# FMC_PWR.net
KiCad netlist of a schematic drawn in Altium Designer
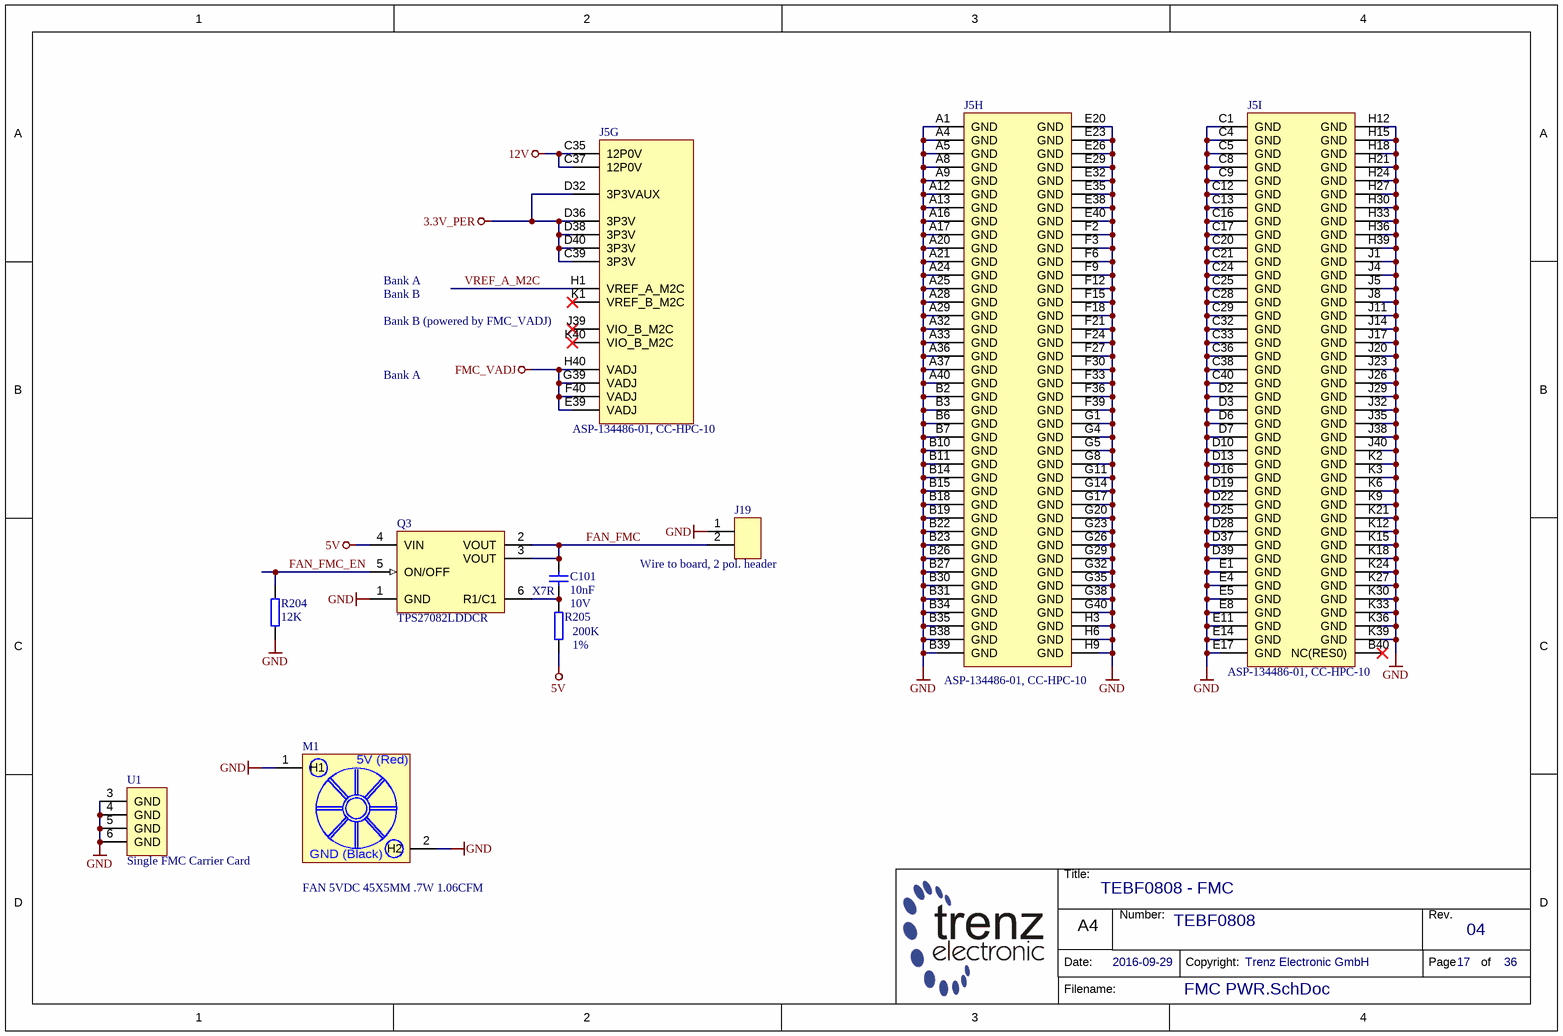
[diagram p0: FMC PWR.SchDoc]

(export (version "E")
  (design (tool "Eeschema 10.0.6"))
  (components
    (comp (ref "C101")
      (value "10nF")
      (footprint "CAPC0603X33N")
      (description "KON 10nF X7R 10V SMD 10%")
      (fields
        (field (name "VOLTAGE") "10V")
        (field (name "TECHNOLOGY") "X7R")
        (field (name "TOLERANCE") "10%")
      )
      (libsource (lib "TE") (part "CAP-NP"))
    )
    (comp (ref "J5")
      (value "ASP-134486-01, CC-HPC-10")
      (footprint "ASP-134486-01B")
      (description "ASP-134486-01 female, CC-HPC-10")
      (libsource (lib "TE") (part "VITA57-FMC-HPC-Layout"))
    )
    (comp (ref "J19")
      (value "Wire to board, 2 pol. header")
      (footprint "Molex22-27-2021")
      (description "Wire to board, 2 pol. header 0°")
      (libsource (lib "TE") (part "CON-2"))
    )
    (comp (ref "M1")
      (value "FAN 5VDC 45X5MM .7W 1.06CFM")
      (footprint "F455B-05MD")
      (libsource (lib "TE") (part "F455B-05MD"))
    )
    (comp (ref "Q3")
      (value "TPS27082LDDCR")
      (footprint "SOT95P280X110-6N")
      (libsource (lib "TE") (part "TPS27082LDDCR"))
    )
    (comp (ref "R204")
      (value "12K")
      (footprint "RESC1005X40N")
      (description "WID SMD 12K 1% 0,063W")
      (fields (field (name "TOLERANCE") "1%"))
      (libsource (lib "TE") (part "RES"))
    )
    (comp (ref "R205")
      (value "200K")
      (footprint "RESC1005X40N")
      (description "WID SMD 200K 1% 0,063W")
      (fields (field (name "TOLERANCE") "1%"))
      (libsource (lib "TE") (part "RES"))
    )
    (comp (ref "U1")
      (value "Single FMC Carrier Card")
      (footprint "FMC-MM-Single-Base")
      (description "FMC-MM-Single PCB Baseboard Snap")
      (libsource (lib "TE") (part "FMC-MM-Single"))
    )
  )
  (nets
    (net (code "1") (name "/FAN_FMC") (class "Default")
      (node (ref "C101") (pin "1") (pinfunction "1_1") (pintype "passive"))
      (node (ref "J19") (pin "2") (pinfunction "2_2") (pintype "passive"))
      (node (ref "Q3") (pin "2") (pinfunction "VOUT_2") (pintype "power_in"))
      (node (ref "Q3") (pin "3") (pinfunction "VOUT_3") (pintype "power_in"))
    )
    (net (code "2") (name "/FAN_FMC_EN") (class "Default")
      (node (ref "Q3") (pin "5") (pinfunction "ON/OFF_5") (pintype "input"))
      (node (ref "R204") (pin "1") (pinfunction "1_1") (pintype "passive"))
    )
    (net (code "3") (name "/VREF_A_M2C") (class "Default")
      (node (ref "J5") (pin "H1") (pinfunction "VREF_A_M2C_H1") (pintype "power_in"))
    )
    (net (code "4") (name "3.3V_PER") (class "Default")
      (node (ref "J5") (pin "C39") (pinfunction "3P3V_C39") (pintype "power_in"))
      (node (ref "J5") (pin "D32") (pinfunction "3P3VAUX_D32") (pintype "power_in"))
      (node (ref "J5") (pin "D36") (pinfunction "3P3V_D36") (pintype "power_in"))
      (node (ref "J5") (pin "D38") (pinfunction "3P3V_D38") (pintype "power_in"))
      (node (ref "J5") (pin "D40") (pinfunction "3P3V_D40") (pintype "power_in"))
    )
    (net (code "5") (name "5V") (class "Default")
      (node (ref "Q3") (pin "4") (pinfunction "VIN_4") (pintype "power_in"))
      (node (ref "R205") (pin "2") (pinfunction "2_2") (pintype "passive"))
    )
    (net (code "6") (name "12V") (class "Default")
      (node (ref "J5") (pin "C35") (pinfunction "12P0V_C35") (pintype "power_in"))
      (node (ref "J5") (pin "C37") (pinfunction "12P0V_C37") (pintype "power_in"))
    )
    (net (code "7") (name "FMC_VADJ") (class "Default")
      (node (ref "J5") (pin "E39") (pinfunction "VADJ_E39") (pintype "power_in"))
      (node (ref "J5") (pin "F40") (pinfunction "VADJ_F40") (pintype "power_in"))
      (node (ref "J5") (pin "G39") (pinfunction "VADJ_G39") (pintype "power_in"))
      (node (ref "J5") (pin "H40") (pinfunction "VADJ_H40") (pintype "power_in"))
    )
    (net (code "8") (name "GND") (class "Default")
      (node (ref "J19") (pin "1") (pinfunction "1_1") (pintype "passive"))
      (node (ref "J5") (pin "A1") (pinfunction "GND_A1") (pintype "power_in"))
      (node (ref "J5") (pin "A12") (pinfunction "GND_A12") (pintype "power_in"))
      (node (ref "J5") (pin "A13") (pinfunction "GND_A13") (pintype "power_in"))
      (node (ref "J5") (pin "A16") (pinfunction "GND_A16") (pintype "power_in"))
      (node (ref "J5") (pin "A17") (pinfunction "GND_A17") (pintype "power_in"))
      (node (ref "J5") (pin "A20") (pinfunction "GND_A20") (pintype "power_in"))
      (node (ref "J5") (pin "A21") (pinfunction "GND_A21") (pintype "power_in"))
      (node (ref "J5") (pin "A24") (pinfunction "GND_A24") (pintype "power_in"))
      (node (ref "J5") (pin "A25") (pinfunction "GND_A25") (pintype "power_in"))
      (node (ref "J5") (pin "A28") (pinfunction "GND_A28") (pintype "power_in"))
      (node (ref "J5") (pin "A29") (pinfunction "GND_A29") (pintype "power_in"))
      (node (ref "J5") (pin "A32") (pinfunction "GND_A32") (pintype "power_in"))
      (node (ref "J5") (pin "A33") (pinfunction "GND_A33") (pintype "power_in"))
      (node (ref "J5") (pin "A36") (pinfunction "GND_A36") (pintype "power_in"))
      (node (ref "J5") (pin "A37") (pinfunction "GND_A37") (pintype "power_in"))
      (node (ref "J5") (pin "A4") (pinfunction "GND_A4") (pintype "power_in"))
      (node (ref "J5") (pin "A40") (pinfunction "GND_A40") (pintype "power_in"))
      (node (ref "J5") (pin "A5") (pinfunction "GND_A5") (pintype "power_in"))
      (node (ref "J5") (pin "A8") (pinfunction "GND_A8") (pintype "power_in"))
      (node (ref "J5") (pin "A9") (pinfunction "GND_A9") (pintype "power_in"))
      (node (ref "J5") (pin "B10") (pinfunction "GND_B10") (pintype "power_in"))
      (node (ref "J5") (pin "B11") (pinfunction "GND_B11") (pintype "power_in"))
      (node (ref "J5") (pin "B14") (pinfunction "GND_B14") (pintype "power_in"))
      (node (ref "J5") (pin "B15") (pinfunction "GND_B15") (pintype "power_in"))
      (node (ref "J5") (pin "B18") (pinfunction "GND_B18") (pintype "power_in"))
      (node (ref "J5") (pin "B19") (pinfunction "GND_B19") (pintype "power_in"))
      (node (ref "J5") (pin "B2") (pinfunction "GND_B2") (pintype "power_in"))
      (node (ref "J5") (pin "B22") (pinfunction "GND_B22") (pintype "power_in"))
      (node (ref "J5") (pin "B23") (pinfunction "GND_B23") (pintype "power_in"))
      (node (ref "J5") (pin "B26") (pinfunction "GND_B26") (pintype "power_in"))
      (node (ref "J5") (pin "B27") (pinfunction "GND_B27") (pintype "power_in"))
      (node (ref "J5") (pin "B3") (pinfunction "GND_B3") (pintype "power_in"))
      (node (ref "J5") (pin "B30") (pinfunction "GND_B30") (pintype "power_in"))
      (node (ref "J5") (pin "B31") (pinfunction "GND_B31") (pintype "power_in"))
      (node (ref "J5") (pin "B34") (pinfunction "GND_B34") (pintype "power_in"))
      (node (ref "J5") (pin "B35") (pinfunction "GND_B35") (pintype "power_in"))
      (node (ref "J5") (pin "B38") (pinfunction "GND_B38") (pintype "power_in"))
      (node (ref "J5") (pin "B39") (pinfunction "GND_B39") (pintype "power_in"))
      (node (ref "J5") (pin "B6") (pinfunction "GND_B6") (pintype "power_in"))
      (node (ref "J5") (pin "B7") (pinfunction "GND_B7") (pintype "power_in"))
      (node (ref "J5") (pin "C1") (pinfunction "GND_C1") (pintype "power_in"))
      (node (ref "J5") (pin "C12") (pinfunction "GND_C12") (pintype "power_in"))
      (node (ref "J5") (pin "C13") (pinfunction "GND_C13") (pintype "power_in"))
      (node (ref "J5") (pin "C16") (pinfunction "GND_C16") (pintype "power_in"))
      (node (ref "J5") (pin "C17") (pinfunction "GND_C17") (pintype "power_in"))
      (node (ref "J5") (pin "C20") (pinfunction "GND_C20") (pintype "power_in"))
      (node (ref "J5") (pin "C21") (pinfunction "GND_C21") (pintype "power_in"))
      (node (ref "J5") (pin "C24") (pinfunction "GND_C24") (pintype "power_in"))
      (node (ref "J5") (pin "C25") (pinfunction "GND_C25") (pintype "power_in"))
      (node (ref "J5") (pin "C28") (pinfunction "GND_C28") (pintype "power_in"))
      (node (ref "J5") (pin "C29") (pinfunction "GND_C29") (pintype "power_in"))
      (node (ref "J5") (pin "C32") (pinfunction "GND_C32") (pintype "power_in"))
      (node (ref "J5") (pin "C33") (pinfunction "GND_C33") (pintype "power_in"))
      (node (ref "J5") (pin "C36") (pinfunction "GND_C36") (pintype "power_in"))
      (node (ref "J5") (pin "C38") (pinfunction "GND_C38") (pintype "power_in"))
      (node (ref "J5") (pin "C4") (pinfunction "GND_C4") (pintype "power_in"))
      (node (ref "J5") (pin "C40") (pinfunction "GND_C40") (pintype "power_in"))
      (node (ref "J5") (pin "C5") (pinfunction "GND_C5") (pintype "power_in"))
      (node (ref "J5") (pin "C8") (pinfunction "GND_C8") (pintype "power_in"))
      (node (ref "J5") (pin "C9") (pinfunction "GND_C9") (pintype "power_in"))
      (node (ref "J5") (pin "D10") (pinfunction "GND_D10") (pintype "power_in"))
      (node (ref "J5") (pin "D13") (pinfunction "GND_D13") (pintype "power_in"))
      (node (ref "J5") (pin "D16") (pinfunction "GND_D16") (pintype "power_in"))
      (node (ref "J5") (pin "D19") (pinfunction "GND_D19") (pintype "power_in"))
      (node (ref "J5") (pin "D2") (pinfunction "GND_D2") (pintype "power_in"))
      (node (ref "J5") (pin "D22") (pinfunction "GND_D22") (pintype "power_in"))
      (node (ref "J5") (pin "D25") (pinfunction "GND_D25") (pintype "power_in"))
      (node (ref "J5") (pin "D28") (pinfunction "GND_D28") (pintype "power_in"))
      (node (ref "J5") (pin "D3") (pinfunction "GND_D3") (pintype "power_in"))
      (node (ref "J5") (pin "D37") (pinfunction "GND_D37") (pintype "power_in"))
      (node (ref "J5") (pin "D39") (pinfunction "GND_D39") (pintype "power_in"))
      (node (ref "J5") (pin "D6") (pinfunction "GND_D6") (pintype "power_in"))
      (node (ref "J5") (pin "D7") (pinfunction "GND_D7") (pintype "power_in"))
      (node (ref "J5") (pin "E1") (pinfunction "GND_E1") (pintype "power_in"))
      (node (ref "J5") (pin "E11") (pinfunction "GND_E11") (pintype "power_in"))
      (node (ref "J5") (pin "E14") (pinfunction "GND_E14") (pintype "power_in"))
      (node (ref "J5") (pin "E17") (pinfunction "GND_E17") (pintype "power_in"))
      (node (ref "J5") (pin "E20") (pinfunction "GND_E20") (pintype "power_in"))
      (node (ref "J5") (pin "E23") (pinfunction "GND_E23") (pintype "power_in"))
      (node (ref "J5") (pin "E26") (pinfunction "GND_E26") (pintype "power_in"))
      (node (ref "J5") (pin "E29") (pinfunction "GND_E29") (pintype "power_in"))
      (node (ref "J5") (pin "E32") (pinfunction "GND_E32") (pintype "power_in"))
      (node (ref "J5") (pin "E35") (pinfunction "GND_E35") (pintype "power_in"))
      (node (ref "J5") (pin "E38") (pinfunction "GND_E38") (pintype "power_in"))
      (node (ref "J5") (pin "E4") (pinfunction "GND_E4") (pintype "power_in"))
      (node (ref "J5") (pin "E40") (pinfunction "GND_E40") (pintype "power_in"))
      (node (ref "J5") (pin "E5") (pinfunction "GND_E5") (pintype "power_in"))
      (node (ref "J5") (pin "E8") (pinfunction "GND_E8") (pintype "power_in"))
      (node (ref "J5") (pin "F12") (pinfunction "GND_F12") (pintype "power_in"))
      (node (ref "J5") (pin "F15") (pinfunction "GND_F15") (pintype "power_in"))
      (node (ref "J5") (pin "F18") (pinfunction "GND_F18") (pintype "power_in"))
      (node (ref "J5") (pin "F2") (pinfunction "GND_F2") (pintype "power_in"))
      (node (ref "J5") (pin "F21") (pinfunction "GND_F21") (pintype "power_in"))
      (node (ref "J5") (pin "F24") (pinfunction "GND_F24") (pintype "power_in"))
      (node (ref "J5") (pin "F27") (pinfunction "GND_F27") (pintype "power_in"))
      (node (ref "J5") (pin "F3") (pinfunction "GND_F3") (pintype "power_in"))
      (node (ref "J5") (pin "F30") (pinfunction "GND_F30") (pintype "power_in"))
      (node (ref "J5") (pin "F33") (pinfunction "GND_F33") (pintype "power_in"))
      (node (ref "J5") (pin "F36") (pinfunction "GND_F36") (pintype "power_in"))
      (node (ref "J5") (pin "F39") (pinfunction "GND_F39") (pintype "power_in"))
      (node (ref "J5") (pin "F6") (pinfunction "GND_F6") (pintype "power_in"))
      (node (ref "J5") (pin "F9") (pinfunction "GND_F9") (pintype "power_in"))
      (node (ref "J5") (pin "G1") (pinfunction "GND_G1") (pintype "power_in"))
      (node (ref "J5") (pin "G11") (pinfunction "GND_G11") (pintype "power_in"))
      (node (ref "J5") (pin "G14") (pinfunction "GND_G14") (pintype "power_in"))
      (node (ref "J5") (pin "G17") (pinfunction "GND_G17") (pintype "power_in"))
      (node (ref "J5") (pin "G20") (pinfunction "GND_G20") (pintype "power_in"))
      (node (ref "J5") (pin "G23") (pinfunction "GND_G23") (pintype "power_in"))
      (node (ref "J5") (pin "G26") (pinfunction "GND_G26") (pintype "power_in"))
      (node (ref "J5") (pin "G29") (pinfunction "GND_G29") (pintype "power_in"))
      (node (ref "J5") (pin "G32") (pinfunction "GND_G32") (pintype "power_in"))
      (node (ref "J5") (pin "G35") (pinfunction "GND_G35") (pintype "power_in"))
      (node (ref "J5") (pin "G38") (pinfunction "GND_G38") (pintype "power_in"))
      (node (ref "J5") (pin "G4") (pinfunction "GND_G4") (pintype "power_in"))
      (node (ref "J5") (pin "G40") (pinfunction "GND_G40") (pintype "power_in"))
      (node (ref "J5") (pin "G5") (pinfunction "GND_G5") (pintype "power_in"))
      (node (ref "J5") (pin "G8") (pinfunction "GND_G8") (pintype "power_in"))
      (node (ref "J5") (pin "H12") (pinfunction "GND_H12") (pintype "power_in"))
      (node (ref "J5") (pin "H15") (pinfunction "GND_H15") (pintype "power_in"))
      (node (ref "J5") (pin "H18") (pinfunction "GND_H18") (pintype "power_in"))
      (node (ref "J5") (pin "H21") (pinfunction "GND_H21") (pintype "power_in"))
      (node (ref "J5") (pin "H24") (pinfunction "GND_H24") (pintype "power_in"))
      (node (ref "J5") (pin "H27") (pinfunction "GND_H27") (pintype "power_in"))
      (node (ref "J5") (pin "H3") (pinfunction "GND_H3") (pintype "power_in"))
      (node (ref "J5") (pin "H30") (pinfunction "GND_H30") (pintype "power_in"))
      (node (ref "J5") (pin "H33") (pinfunction "GND_H33") (pintype "power_in"))
      (node (ref "J5") (pin "H36") (pinfunction "GND_H36") (pintype "power_in"))
      (node (ref "J5") (pin "H39") (pinfunction "GND_H39") (pintype "power_in"))
      (node (ref "J5") (pin "H6") (pinfunction "GND_H6") (pintype "power_in"))
      (node (ref "J5") (pin "H9") (pinfunction "GND_H9") (pintype "power_in"))
      (node (ref "J5") (pin "J1") (pinfunction "GND_J1") (pintype "power_in"))
      (node (ref "J5") (pin "J11") (pinfunction "GND_J11") (pintype "power_in"))
      (node (ref "J5") (pin "J14") (pinfunction "GND_J14") (pintype "power_in"))
      (node (ref "J5") (pin "J17") (pinfunction "GND_J17") (pintype "power_in"))
      (node (ref "J5") (pin "J20") (pinfunction "GND_J20") (pintype "power_in"))
      (node (ref "J5") (pin "J23") (pinfunction "GND_J23") (pintype "power_in"))
      (node (ref "J5") (pin "J26") (pinfunction "GND_J26") (pintype "power_in"))
      (node (ref "J5") (pin "J29") (pinfunction "GND_J29") (pintype "power_in"))
      (node (ref "J5") (pin "J32") (pinfunction "GND_J32") (pintype "power_in"))
      (node (ref "J5") (pin "J35") (pinfunction "GND_J35") (pintype "power_in"))
      (node (ref "J5") (pin "J38") (pinfunction "GND_J38") (pintype "power_in"))
      (node (ref "J5") (pin "J4") (pinfunction "GND_J4") (pintype "power_in"))
      (node (ref "J5") (pin "J40") (pinfunction "GND_J40") (pintype "power_in"))
      (node (ref "J5") (pin "J5") (pinfunction "GND_J5") (pintype "power_in"))
      (node (ref "J5") (pin "J8") (pinfunction "GND_J8") (pintype "power_in"))
      (node (ref "J5") (pin "K12") (pinfunction "GND_K12") (pintype "power_in"))
      (node (ref "J5") (pin "K15") (pinfunction "GND_K15") (pintype "power_in"))
      (node (ref "J5") (pin "K18") (pinfunction "GND_K18") (pintype "power_in"))
      (node (ref "J5") (pin "K2") (pinfunction "GND_K2") (pintype "power_in"))
      (node (ref "J5") (pin "K21") (pinfunction "GND_K21") (pintype "power_in"))
      (node (ref "J5") (pin "K24") (pinfunction "GND_K24") (pintype "power_in"))
      (node (ref "J5") (pin "K27") (pinfunction "GND_K27") (pintype "power_in"))
      (node (ref "J5") (pin "K3") (pinfunction "GND_K3") (pintype "power_in"))
      (node (ref "J5") (pin "K30") (pinfunction "GND_K30") (pintype "power_in"))
      (node (ref "J5") (pin "K33") (pinfunction "GND_K33") (pintype "power_in"))
      (node (ref "J5") (pin "K36") (pinfunction "GND_K36") (pintype "power_in"))
      (node (ref "J5") (pin "K39") (pinfunction "GND_K39") (pintype "power_in"))
      (node (ref "J5") (pin "K6") (pinfunction "GND_K6") (pintype "power_in"))
      (node (ref "J5") (pin "K9") (pinfunction "GND_K9") (pintype "power_in"))
      (node (ref "M1") (pin "1") (pinfunction "H1_1") (pintype "passive"))
      (node (ref "M1") (pin "2") (pinfunction "H2_2") (pintype "passive"))
      (node (ref "Q3") (pin "1") (pinfunction "GND_1") (pintype "power_in"))
      (node (ref "R204") (pin "2") (pinfunction "2_2") (pintype "passive"))
      (node (ref "U1") (pin "3") (pinfunction "GND_3") (pintype "passive"))
      (node (ref "U1") (pin "4") (pinfunction "GND_4") (pintype "passive"))
      (node (ref "U1") (pin "5") (pinfunction "GND_5") (pintype "passive"))
      (node (ref "U1") (pin "6") (pinfunction "GND_6") (pintype "passive"))
    )
    (net (code "9") (name "Net-(Q3-R1{slash}C1)") (class "Default")
      (node (ref "C101") (pin "2") (pinfunction "2_2") (pintype "passive"))
      (node (ref "Q3") (pin "6") (pinfunction "R1/C1_6") (pintype "power_in"))
      (node (ref "R205") (pin "1") (pinfunction "1_1") (pintype "passive"))
    )
    (net (code "10") (name "unconnected-(J5G-VIO_B_M2C-PadJ39)") (class "Default")
      (node (ref "J5") (pin "J39") (pinfunction "VIO_B_M2C_J39") (pintype "power_in+no_connect"))
    )
    (net (code "11") (name "unconnected-(J5G-VIO_B_M2C-PadK40)") (class "Default")
      (node (ref "J5") (pin "K40") (pinfunction "VIO_B_M2C_K40") (pintype "power_in+no_connect"))
    )
    (net (code "12") (name "unconnected-(J5G-VREF_B_M2C-PadK1)") (class "Default")
      (node (ref "J5") (pin "K1") (pinfunction "VREF_B_M2C_K1") (pintype "power_in+no_connect"))
    )
    (net (code "13") (name "unconnected-(J5I-NC(RES0)-PadB40)") (class "Default")
      (node (ref "J5") (pin "B40") (pinfunction "NC(RES0)_B40") (pintype "passive+no_connect"))
    )
  )
)
